# lora.net
KiCad netlist of a schematic drawn in Altium Designer
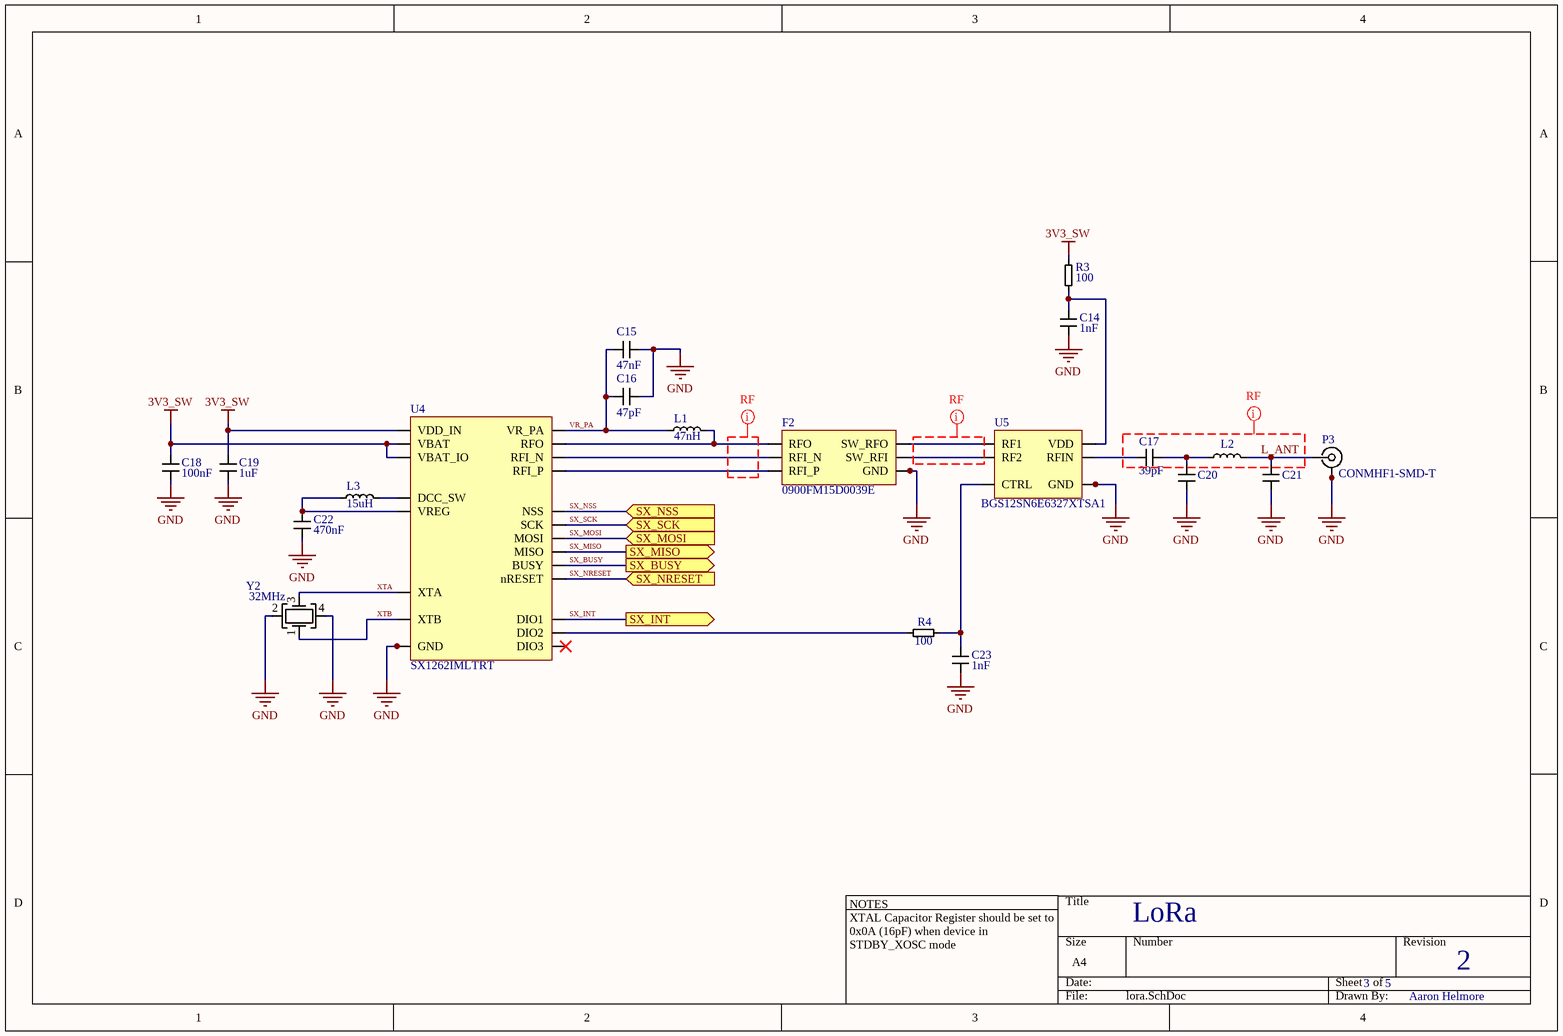
[diagram p0: lora.SchDoc]

(export (version "E")
  (design (tool "Eeschema 10.0.6"))
  (components
    (comp (ref "C14")
      (value "1nF")
      (footprint "CAP_0402")
      (fields (field (name "VOLTAGE") "50V"))
      (libsource (lib "") (part "Capacitor_1"))
    )
    (comp (ref "C15")
      (value "47nF")
      (footprint "CAP_0402")
      (fields (field (name "VOLTAGE") "25V"))
      (libsource (lib "") (part "Capacitor_1"))
    )
    (comp (ref "C16")
      (value "47pF")
      (footprint "CAP_0402")
      (fields (field (name "VOLTAGE") "50V"))
      (libsource (lib "") (part "Capacitor_1"))
    )
    (comp (ref "C17")
      (value "39pF")
      (footprint "CAP_0402")
      (fields (field (name "VOLTAGE") "50V"))
      (libsource (lib "thesis_schem_lib") (part "Capacitor"))
    )
    (comp (ref "C18")
      (value "100nF")
      (footprint "CAP_0402")
      (fields (field (name "VOLTAGE") "25V"))
      (libsource (lib "") (part "Capacitor_1"))
    )
    (comp (ref "C19")
      (value "1uF")
      (footprint "CAP_0402")
      (fields (field (name "VOLTAGE") "25V"))
      (libsource (lib "thesis_schem_lib") (part "Capacitor"))
    )
    (comp (ref "C20") (value "Capacitor") (footprint "CAP_0402") (libsource (lib "") (part "Capacitor_1")))
    (comp (ref "C21") (value "Capacitor") (footprint "CAP_0402") (libsource (lib "") (part "Capacitor_1")))
    (comp (ref "C22")
      (value "470nF")
      (footprint "CAP_0603")
      (fields (field (name "VOLTAGE") "25V"))
      (libsource (lib "") (part "Capacitor_1"))
    )
    (comp (ref "C23")
      (value "1nF")
      (footprint "CAP_0402")
      (fields (field (name "VOLTAGE") "50V"))
      (libsource (lib "") (part "Capacitor_1"))
    )
    (comp (ref "F2")
      (value "0900FM15D0039E")
      (footprint "0900FM15D0039E")
      (description "Miniature impedance-matched filter for Semtech SX1261/SX1262 for 915MHz operation")
      (libsource (lib "thesis_schem_lib") (part "0900FM15D0039E"))
    )
    (comp (ref "L1")
      (value "47nH")
      (footprint "LQW15AN")
      (libsource (lib "thesis_schem_lib") (part "Inductor"))
    )
    (comp (ref "L2")
      (value "Inductor")
      (footprint "RES_0402")
      (libsource (lib "thesis_schem_lib") (part "Inductor"))
    )
    (comp (ref "L3")
      (value "15uH")
      (footprint "VLS2010ET-150M")
      (libsource (lib "thesis_schem_lib") (part "Inductor"))
    )
    (comp (ref "P3")
      (value "CONMHF1-SMD-T")
      (footprint "CONMHF1-SMD-T")
      (libsource (lib "thesis_schem_lib") (part "CONMHF1-SMD-T"))
    )
    (comp (ref "R3")
      (value "100")
      (footprint "RES_0402")
      (fields (field (name "TOLERANCE") "1%"))
      (libsource (lib "") (part "R_Small_1"))
    )
    (comp (ref "R4")
      (value "100")
      (footprint "RES_0402")
      (fields (field (name "TOLERANCE") "1%"))
      (libsource (lib "thesis_schem_lib") (part "R_Small"))
    )
    (comp (ref "U4")
      (value "SX1262IMLTRT")
      (footprint "SX1262IMLTRT")
      (description "Semtech LoRa radio transceivers")
      (libsource (lib "thesis_schem_lib") (part "SX1262IMLTRT"))
    )
    (comp (ref "U5")
      (value "BGS12SN6E6327XTSA1")
      (footprint "BGS12SN6E6327XTSA1")
      (libsource (lib "thesis_schem_lib") (part "BGS12SN6E6327XTSA1"))
    )
    (comp (ref "Y2")
      (value "32MHz")
      (footprint "4-SMD")
      (libsource (lib "thesis_schem_lib") (part "Crystal_2_2"))
    )
  )
  (nets
    (net (code "1") (name "/L_ANT") (class "Default")
      (node (ref "C21") (pin "2") (pinfunction "J11_2") (pintype "passive"))
      (node (ref "L2") (pin "2") (pinfunction "2_2") (pintype "passive"))
      (node (ref "P3") (pin "1") (pinfunction "VCC_1") (pintype "passive"))
    )
    (net (code "2") (name "/SX_BUSY") (class "Default")
      (node (ref "U4") (pin "14") (pinfunction "BUSY_14") (pintype "passive"))
    )
    (net (code "3") (name "/SX_INT") (class "Default")
      (node (ref "U4") (pin "13") (pinfunction "DIO1_13") (pintype "passive"))
    )
    (net (code "4") (name "/SX_MISO") (class "Default")
      (node (ref "U4") (pin "16") (pinfunction "MISO_16") (pintype "passive"))
    )
    (net (code "5") (name "/SX_MOSI") (class "Default")
      (node (ref "U4") (pin "17") (pinfunction "MOSI_17") (pintype "passive"))
    )
    (net (code "6") (name "/SX_NRESET") (class "Default")
      (node (ref "U4") (pin "15") (pinfunction "nRESET_15") (pintype "passive"))
    )
    (net (code "7") (name "/SX_NSS") (class "Default")
      (node (ref "U4") (pin "19") (pinfunction "NSS_19") (pintype "passive"))
    )
    (net (code "8") (name "/SX_SCK") (class "Default")
      (node (ref "U4") (pin "18") (pinfunction "SCK_18") (pintype "passive"))
    )
    (net (code "9") (name "/VR_PA") (class "Default")
      (node (ref "C15") (pin "2") (pinfunction "J11_2") (pintype "passive"))
      (node (ref "C16") (pin "2") (pinfunction "J11_2") (pintype "passive"))
      (node (ref "L1") (pin "1") (pinfunction "1_1") (pintype "passive"))
      (node (ref "U4") (pin "24") (pinfunction "VR_PA_24") (pintype "passive"))
    )
    (net (code "10") (name "/XTA") (class "Default")
      (node (ref "U4") (pin "3") (pinfunction "XTA_3") (pintype "passive"))
      (node (ref "Y2") (pin "3") (pinfunction "3_3") (pintype "passive"))
    )
    (net (code "11") (name "/XTB") (class "Default")
      (node (ref "U4") (pin "4") (pinfunction "XTB_4") (pintype "passive"))
      (node (ref "Y2") (pin "1") (pinfunction "1_1") (pintype "passive"))
    )
    (net (code "12") (name "3V3_SW") (class "Default")
      (node (ref "C18") (pin "2") (pinfunction "J11_2") (pintype "passive"))
      (node (ref "C19") (pin "1") (pinfunction "J12_1") (pintype "passive"))
      (node (ref "R3") (pin "1") (pinfunction "1_1") (pintype "passive"))
      (node (ref "U4") (pin "1") (pinfunction "VDD_IN_1") (pintype "passive"))
      (node (ref "U4") (pin "10") (pinfunction "VBAT_10") (pintype "passive"))
      (node (ref "U4") (pin "11") (pinfunction "VBAT_IO_11") (pintype "passive"))
    )
    (net (code "13") (name "GND") (class "Default")
      (node (ref "C14") (pin "1") (pinfunction "J12_1") (pintype "passive"))
      (node (ref "C15") (pin "1") (pinfunction "J12_1") (pintype "passive"))
      (node (ref "C16") (pin "1") (pinfunction "J12_1") (pintype "passive"))
      (node (ref "C18") (pin "1") (pinfunction "J12_1") (pintype "passive"))
      (node (ref "C19") (pin "2") (pinfunction "J11_2") (pintype "passive"))
      (node (ref "C20") (pin "1") (pinfunction "J12_1") (pintype "passive"))
      (node (ref "C21") (pin "1") (pinfunction "J12_1") (pintype "passive"))
      (node (ref "C22") (pin "1") (pinfunction "J12_1") (pintype "passive"))
      (node (ref "C23") (pin "1") (pinfunction "J12_1") (pintype "passive"))
      (node (ref "F2") (pin "10") (pinfunction "GND_10") (pintype "passive"))
      (node (ref "F2") (pin "2") (pinfunction "GND_2") (pintype "passive"))
      (node (ref "F2") (pin "5") (pinfunction "GND_5") (pintype "passive"))
      (node (ref "F2") (pin "7") (pinfunction "GND_7") (pintype "passive"))
      (node (ref "F2") (pin "9") (pinfunction "GND_9") (pintype "passive"))
      (node (ref "P3") (pin "2") (pinfunction "VCC_2") (pintype "passive"))
      (node (ref "P3") (pin "3") (pinfunction "VCC_3") (pintype "passive"))
      (node (ref "P3") (pin "4") (pinfunction "VCC_4") (pintype "passive"))
      (node (ref "U4") (pin "0") (pinfunction "GND_0") (pintype "passive"))
      (node (ref "U4") (pin "2") (pinfunction "GND_2") (pintype "passive"))
      (node (ref "U4") (pin "20") (pinfunction "GND_20") (pintype "passive"))
      (node (ref "U4") (pin "5") (pinfunction "GND_5") (pintype "passive"))
      (node (ref "U4") (pin "8") (pinfunction "GND_8") (pintype "passive"))
      (node (ref "U5") (pin "2") (pinfunction "GND_2") (pintype "passive"))
      (node (ref "Y2") (pin "2") (pinfunction "2_2") (pintype "passive"))
      (node (ref "Y2") (pin "4") (pinfunction "4_4") (pintype "passive"))
    )
    (net (code "14") (name "Net-(C14-J11)") (class "Default")
      (node (ref "C14") (pin "2") (pinfunction "J11_2") (pintype "passive"))
      (node (ref "R3") (pin "2") (pinfunction "2_2") (pintype "passive"))
      (node (ref "U5") (pin "4") (pinfunction "VDD_4") (pintype "passive"))
    )
    (net (code "15") (name "Net-(C17-J11)") (class "Default")
      (node (ref "C17") (pin "2") (pinfunction "J11_2") (pintype "passive"))
      (node (ref "C20") (pin "2") (pinfunction "J11_2") (pintype "passive"))
      (node (ref "L2") (pin "1") (pinfunction "1_1") (pintype "passive"))
    )
    (net (code "16") (name "Net-(C17-J12)") (class "Default")
      (node (ref "C17") (pin "1") (pinfunction "J12_1") (pintype "passive"))
      (node (ref "U5") (pin "5") (pinfunction "RFIN_5") (pintype "passive"))
    )
    (net (code "17") (name "Net-(C22-J11)") (class "Default")
      (node (ref "C22") (pin "2") (pinfunction "J11_2") (pintype "passive"))
      (node (ref "L3") (pin "1") (pinfunction "1_1") (pintype "passive"))
      (node (ref "U4") (pin "7") (pinfunction "VREG_7") (pintype "passive"))
    )
    (net (code "18") (name "Net-(C23-J11)") (class "Default")
      (node (ref "C23") (pin "2") (pinfunction "J11_2") (pintype "passive"))
      (node (ref "R4") (pin "2") (pinfunction "2_2") (pintype "passive"))
      (node (ref "U5") (pin "6") (pinfunction "CTRL_6") (pintype "passive"))
    )
    (net (code "19") (name "Net-(F2-RFI_N)") (class "Default")
      (node (ref "F2") (pin "3") (pinfunction "RFI_N_3") (pintype "passive"))
      (node (ref "U4") (pin "22") (pinfunction "RFI_N_22") (pintype "passive"))
    )
    (net (code "20") (name "Net-(F2-RFI_P)") (class "Default")
      (node (ref "F2") (pin "4") (pinfunction "RFI_P_4") (pintype "passive"))
      (node (ref "U4") (pin "21") (pinfunction "RFI_P_21") (pintype "passive"))
    )
    (net (code "21") (name "Net-(F2-RFO)") (class "Default")
      (node (ref "F2") (pin "1") (pinfunction "RFO_1") (pintype "passive"))
      (node (ref "L1") (pin "2") (pinfunction "2_2") (pintype "passive"))
      (node (ref "U4") (pin "23") (pinfunction "RFO_23") (pintype "passive"))
    )
    (net (code "22") (name "Net-(F2-SW_RFI)") (class "Default")
      (node (ref "F2") (pin "6") (pinfunction "SW_RFI_6") (pintype "passive"))
      (node (ref "U5") (pin "1") (pinfunction "RF2_1") (pintype "passive"))
    )
    (net (code "23") (name "Net-(F2-SW_RFO)") (class "Default")
      (node (ref "F2") (pin "8") (pinfunction "SW_RFO_8") (pintype "passive"))
      (node (ref "U5") (pin "3") (pinfunction "RF1_3") (pintype "passive"))
    )
    (net (code "24") (name "Net-(U4-DCC_SW)") (class "Default")
      (node (ref "L3") (pin "2") (pinfunction "2_2") (pintype "passive"))
      (node (ref "U4") (pin "9") (pinfunction "DCC_SW_9") (pintype "passive"))
    )
    (net (code "25") (name "Net-(U4-DIO2)") (class "Default")
      (node (ref "R4") (pin "1") (pinfunction "1_1") (pintype "passive"))
      (node (ref "U4") (pin "12") (pinfunction "DIO2_12") (pintype "passive"))
    )
    (net (code "26") (name "unconnected-(U4-DIO3-Pad6)") (class "Default")
      (node (ref "U4") (pin "6") (pinfunction "DIO3_6") (pintype "passive+no_connect"))
    )
  )
)
